# FPGA_RAM.net
KiCad netlist of a schematic drawn in Altium Designer
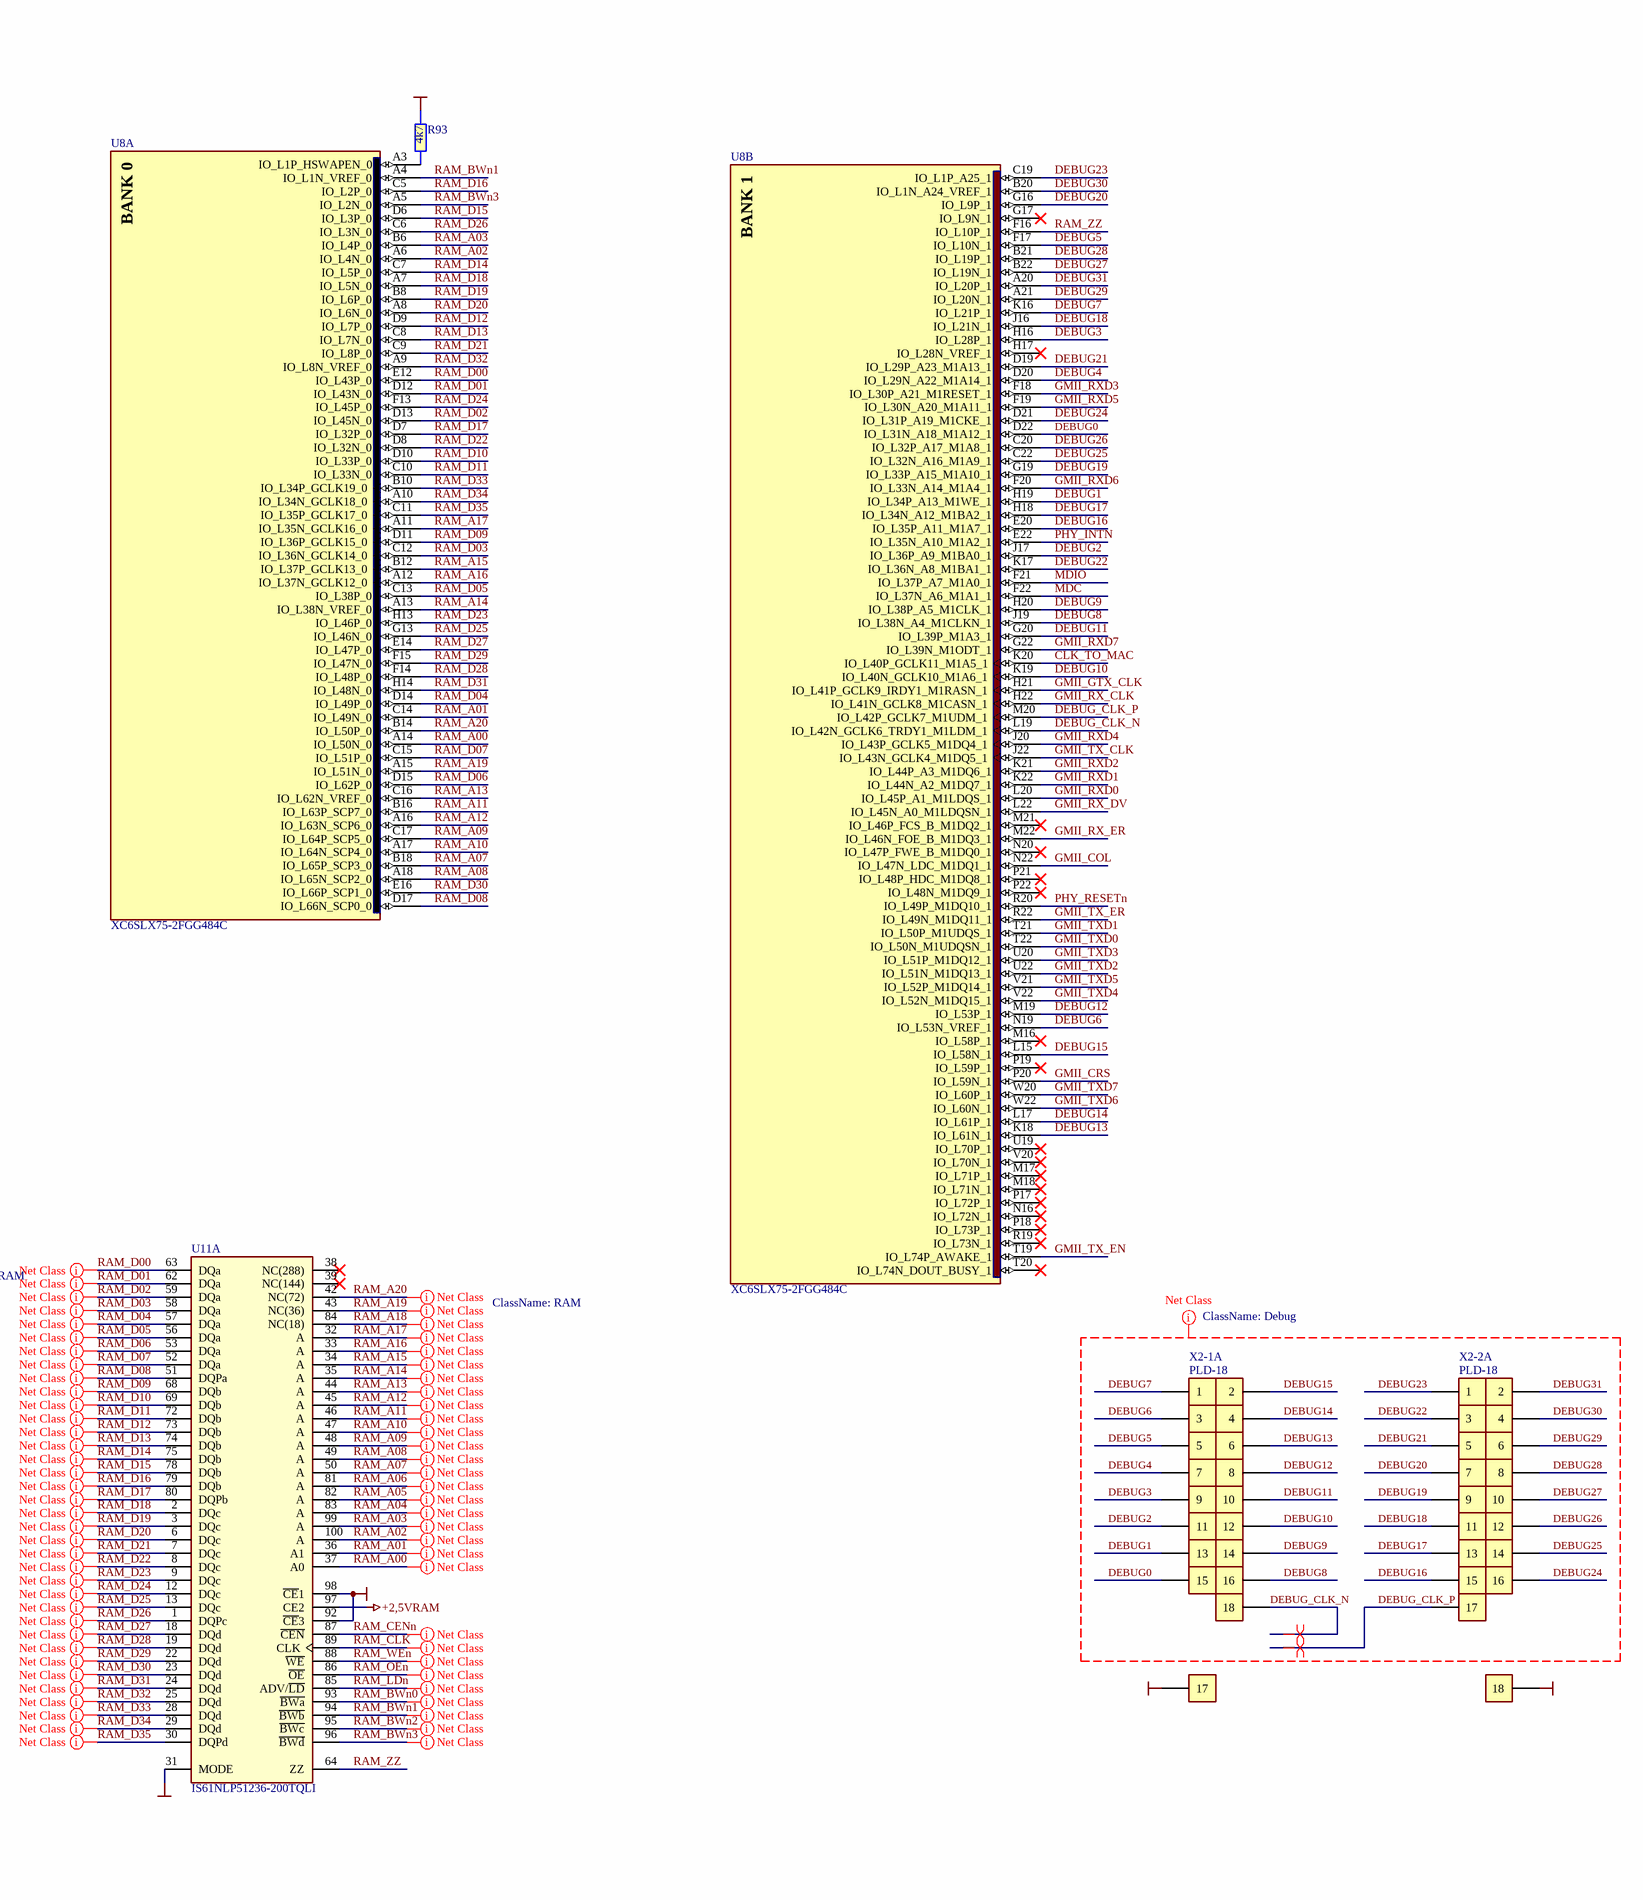
[diagram p0: FPGA_RAM.SchDoc, left]
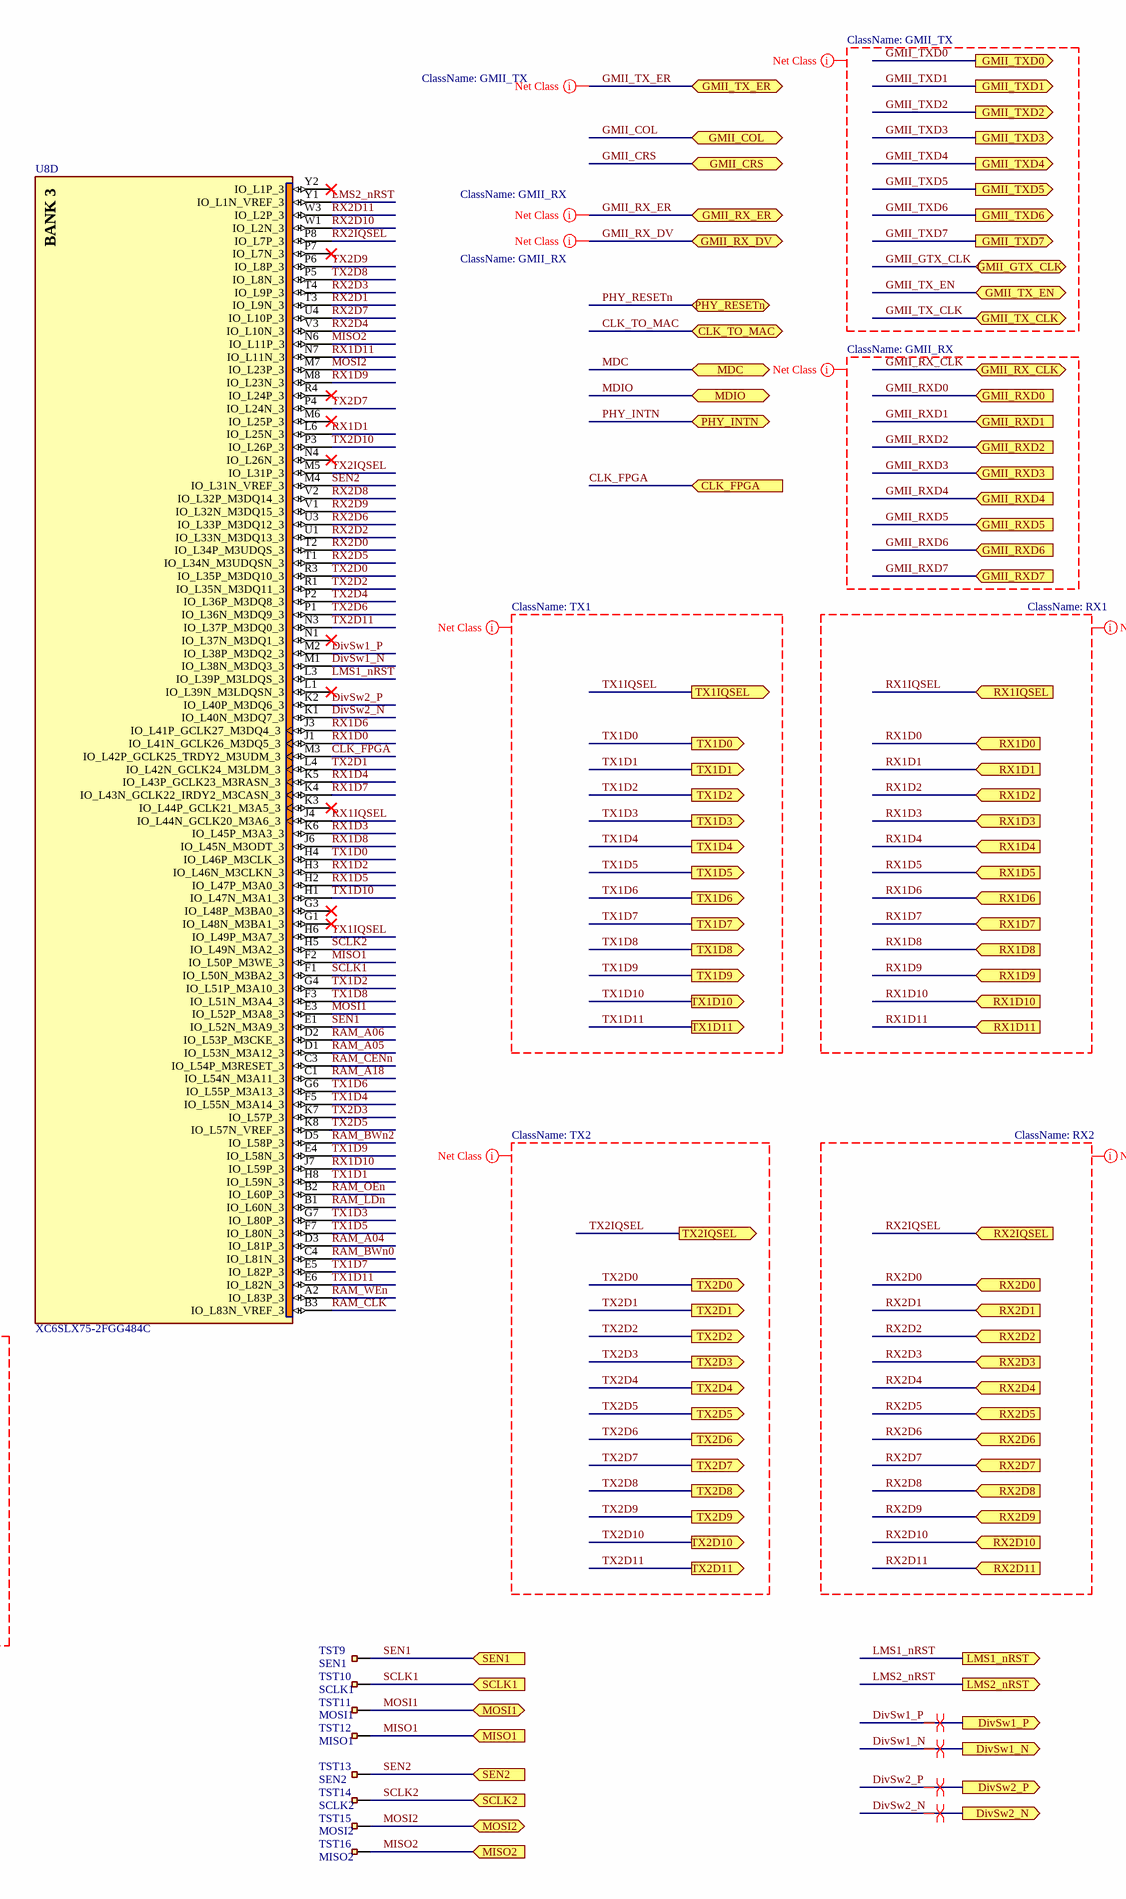
[diagram p1: FPGA_RAM.SchDoc, right]

(export (version "E")
  (design (tool "Eeschema 10.0.6"))
  (components
    (comp (ref "R93")
      (value "4k7")
      (footprint "R0603-PHILLIPS")
      (description "Резистор")
      (fields (field (name "MANUFACTURER") "YAGEO") (field (name "TOLERANCE") "5%"))
      (libsource (lib "altium-import") (part "root_2_R0603_"))
    )
    (comp (ref "TST9")
      (value "SEN1")
      (footprint "kp40x40")
      (description "Контактна  площадка")
      (fields (field (name "MANUFACTURER") "Конструктив"))
      (libsource (lib "Connectors") (part "KP"))
    )
    (comp (ref "TST10")
      (value "SCLK1")
      (footprint "kp40x40")
      (description "Контактна  площадка")
      (fields (field (name "MANUFACTURER") "Конструктив"))
      (libsource (lib "Connectors") (part "KP"))
    )
    (comp (ref "TST11")
      (value "MOSI1")
      (footprint "kp40x40")
      (description "Контактна  площадка")
      (fields (field (name "MANUFACTURER") "Конструктив"))
      (libsource (lib "Connectors") (part "KP"))
    )
    (comp (ref "TST12")
      (value "MISO1")
      (footprint "kp40x40")
      (description "Контактна  площадка")
      (fields (field (name "MANUFACTURER") "Конструктив"))
      (libsource (lib "Connectors") (part "KP"))
    )
    (comp (ref "TST13")
      (value "SEN2")
      (footprint "kp40x40")
      (description "Контактна  площадка")
      (fields (field (name "MANUFACTURER") "Конструктив"))
      (libsource (lib "Connectors") (part "KP"))
    )
    (comp (ref "TST14")
      (value "SCLK2")
      (footprint "kp40x40")
      (description "Контактна  площадка")
      (fields (field (name "MANUFACTURER") "Конструктив"))
      (libsource (lib "Connectors") (part "KP"))
    )
    (comp (ref "TST15")
      (value "MOSI2")
      (footprint "kp40x40")
      (description "Контактна  площадка")
      (fields (field (name "MANUFACTURER") "Конструктив"))
      (libsource (lib "Connectors") (part "KP"))
    )
    (comp (ref "TST16")
      (value "MISO2")
      (footprint "kp40x40")
      (description "Контактна  площадка")
      (fields (field (name "MANUFACTURER") "Конструктив"))
      (libsource (lib "Connectors") (part "KP"))
    )
    (comp (ref "U8")
      (value "XC6SLX75-2FGG484C")
      (footprint "FBGA484")
      (fields (field (name "MANUFACTURER") "Xilinx"))
      (libsource (lib "MicroCircuitsM-Z") (part "XC6SLX75-2FGG484C"))
    )
    (comp (ref "U11")
      (value "IS61NLP51236-200TQLI")
      (footprint "QFP-10020X14/0.65]")
      (description "Микросхема")
      (fields (field (name "MANUFACTURER") "ISSI"))
      (libsource (lib "MicroCircuits0-L") (part "CY7C1354C-166AXI"))
    )
    (comp (ref "X2-1")
      (value "PLD-18")
      (footprint "PLD-18")
      (description "Разъем")
      (fields (field (name "MANUFACTURER") "BM"))
      (libsource (lib "") (part "PLD-18_1"))
    )
    (comp (ref "X2-2")
      (value "PLD-18")
      (footprint "PLD-18")
      (description "Разъем")
      (fields (field (name "MANUFACTURER") "BM"))
      (libsource (lib "") (part "PLD-18_1"))
    )
  )
  (nets
    (net (code "1") (name "+2,5VRAM") (class "Default")
      (node (ref "U11") (pin "97") (pinfunction "CE2_97") (pintype "passive"))
    )
    (net (code "2") (name "/CLK_FPGA") (class "Default")
      (node (ref "U8") (pin "M3") (pinfunction "IO_L42P_GCLK25_TRDY2_M3UDM_3_M3") (pintype "bidirectional"))
    )
    (net (code "3") (name "/CLK_TO_MAC") (class "Default")
      (node (ref "U8") (pin "K20") (pinfunction "IO_L40P_GCLK11_M1A5_1_K20") (pintype "bidirectional"))
    )
    (net (code "4") (name "/DEBUG0") (class "Default")
      (node (ref "U8") (pin "D22") (pinfunction "IO_L31N_A18_M1A12_1_D22") (pintype "bidirectional"))
      (node (ref "X2-1") (pin "15") (pinfunction "15_15") (pintype "passive"))
    )
    (net (code "5") (name "/DEBUG1") (class "Default")
      (node (ref "U8") (pin "H19") (pinfunction "IO_L34P_A13_M1WE_1_H19") (pintype "bidirectional"))
      (node (ref "X2-1") (pin "13") (pinfunction "13_13") (pintype "passive"))
    )
    (net (code "6") (name "/DEBUG2") (class "Default")
      (node (ref "U8") (pin "J17") (pinfunction "IO_L36P_A9_M1BA0_1_J17") (pintype "bidirectional"))
      (node (ref "X2-1") (pin "11") (pinfunction "11_11") (pintype "passive"))
    )
    (net (code "7") (name "/DEBUG3") (class "Default")
      (node (ref "U8") (pin "H16") (pinfunction "IO_L28P_1_H16") (pintype "bidirectional"))
      (node (ref "X2-1") (pin "9") (pinfunction "9_9") (pintype "passive"))
    )
    (net (code "8") (name "/DEBUG4") (class "Default")
      (node (ref "U8") (pin "D20") (pinfunction "IO_L29N_A22_M1A14_1_D20") (pintype "bidirectional"))
      (node (ref "X2-1") (pin "7") (pinfunction "7_7") (pintype "passive"))
    )
    (net (code "9") (name "/DEBUG5") (class "Default")
      (node (ref "U8") (pin "F17") (pinfunction "IO_L10N_1_F17") (pintype "bidirectional"))
      (node (ref "X2-1") (pin "5") (pinfunction "5_5") (pintype "passive"))
    )
    (net (code "10") (name "/DEBUG6") (class "Default")
      (node (ref "U8") (pin "N19") (pinfunction "IO_L53N_VREF_1_N19") (pintype "bidirectional"))
      (node (ref "X2-1") (pin "3") (pinfunction "3_3") (pintype "passive"))
    )
    (net (code "11") (name "/DEBUG7") (class "Default")
      (node (ref "U8") (pin "K16") (pinfunction "IO_L21P_1_K16") (pintype "bidirectional"))
      (node (ref "X2-1") (pin "1") (pinfunction "1_1") (pintype "passive"))
    )
    (net (code "12") (name "/DEBUG8") (class "Default")
      (node (ref "U8") (pin "J19") (pinfunction "IO_L38N_A4_M1CLKN_1_J19") (pintype "bidirectional"))
      (node (ref "X2-1") (pin "16") (pinfunction "16_16") (pintype "passive"))
    )
    (net (code "13") (name "/DEBUG9") (class "Default")
      (node (ref "U8") (pin "H20") (pinfunction "IO_L38P_A5_M1CLK_1_H20") (pintype "bidirectional"))
      (node (ref "X2-1") (pin "14") (pinfunction "14_14") (pintype "passive"))
    )
    (net (code "14") (name "/DEBUG10") (class "Default")
      (node (ref "U8") (pin "K19") (pinfunction "IO_L40N_GCLK10_M1A6_1_K19") (pintype "bidirectional"))
      (node (ref "X2-1") (pin "12") (pinfunction "12_12") (pintype "passive"))
    )
    (net (code "15") (name "/DEBUG11") (class "Default")
      (node (ref "U8") (pin "G20") (pinfunction "IO_L39P_M1A3_1_G20") (pintype "bidirectional"))
      (node (ref "X2-1") (pin "10") (pinfunction "10_10") (pintype "passive"))
    )
    (net (code "16") (name "/DEBUG12") (class "Default")
      (node (ref "U8") (pin "M19") (pinfunction "IO_L53P_1_M19") (pintype "bidirectional"))
      (node (ref "X2-1") (pin "8") (pinfunction "8_8") (pintype "passive"))
    )
    (net (code "17") (name "/DEBUG13") (class "Default")
      (node (ref "U8") (pin "K18") (pinfunction "IO_L61N_1_K18") (pintype "bidirectional"))
      (node (ref "X2-1") (pin "6") (pinfunction "6_6") (pintype "passive"))
    )
    (net (code "18") (name "/DEBUG14") (class "Default")
      (node (ref "U8") (pin "L17") (pinfunction "IO_L61P_1_L17") (pintype "bidirectional"))
      (node (ref "X2-1") (pin "4") (pinfunction "4_4") (pintype "passive"))
    )
    (net (code "19") (name "/DEBUG15") (class "Default")
      (node (ref "U8") (pin "L15") (pinfunction "IO_L58N_1_L15") (pintype "bidirectional"))
      (node (ref "X2-1") (pin "2") (pinfunction "2_2") (pintype "passive"))
    )
    (net (code "20") (name "/DEBUG16") (class "Default")
      (node (ref "U8") (pin "E20") (pinfunction "IO_L35P_A11_M1A7_1_E20") (pintype "bidirectional"))
      (node (ref "X2-2") (pin "15") (pinfunction "15_15") (pintype "passive"))
    )
    (net (code "21") (name "/DEBUG17") (class "Default")
      (node (ref "U8") (pin "H18") (pinfunction "IO_L34N_A12_M1BA2_1_H18") (pintype "bidirectional"))
      (node (ref "X2-2") (pin "13") (pinfunction "13_13") (pintype "passive"))
    )
    (net (code "22") (name "/DEBUG18") (class "Default")
      (node (ref "U8") (pin "J16") (pinfunction "IO_L21N_1_J16") (pintype "bidirectional"))
      (node (ref "X2-2") (pin "11") (pinfunction "11_11") (pintype "passive"))
    )
    (net (code "23") (name "/DEBUG19") (class "Default")
      (node (ref "U8") (pin "G19") (pinfunction "IO_L33P_A15_M1A10_1_G19") (pintype "bidirectional"))
      (node (ref "X2-2") (pin "9") (pinfunction "9_9") (pintype "passive"))
    )
    (net (code "24") (name "/DEBUG20") (class "Default")
      (node (ref "U8") (pin "G16") (pinfunction "IO_L9P_1_G16") (pintype "bidirectional"))
      (node (ref "X2-2") (pin "7") (pinfunction "7_7") (pintype "passive"))
    )
    (net (code "25") (name "/DEBUG21") (class "Default")
      (node (ref "U8") (pin "D19") (pinfunction "IO_L29P_A23_M1A13_1_D19") (pintype "bidirectional"))
      (node (ref "X2-2") (pin "5") (pinfunction "5_5") (pintype "passive"))
    )
    (net (code "26") (name "/DEBUG22") (class "Default")
      (node (ref "U8") (pin "K17") (pinfunction "IO_L36N_A8_M1BA1_1_K17") (pintype "bidirectional"))
      (node (ref "X2-2") (pin "3") (pinfunction "3_3") (pintype "passive"))
    )
    (net (code "27") (name "/DEBUG23") (class "Default")
      (node (ref "U8") (pin "C19") (pinfunction "IO_L1P_A25_1_C19") (pintype "bidirectional"))
      (node (ref "X2-2") (pin "1") (pinfunction "1_1") (pintype "passive"))
    )
    (net (code "28") (name "/DEBUG24") (class "Default")
      (node (ref "U8") (pin "D21") (pinfunction "IO_L31P_A19_M1CKE_1_D21") (pintype "bidirectional"))
      (node (ref "X2-2") (pin "16") (pinfunction "16_16") (pintype "passive"))
    )
    (net (code "29") (name "/DEBUG25") (class "Default")
      (node (ref "U8") (pin "C22") (pinfunction "IO_L32N_A16_M1A9_1_C22") (pintype "bidirectional"))
      (node (ref "X2-2") (pin "14") (pinfunction "14_14") (pintype "passive"))
    )
    (net (code "30") (name "/DEBUG26") (class "Default")
      (node (ref "U8") (pin "C20") (pinfunction "IO_L32P_A17_M1A8_1_C20") (pintype "bidirectional"))
      (node (ref "X2-2") (pin "12") (pinfunction "12_12") (pintype "passive"))
    )
    (net (code "31") (name "/DEBUG27") (class "Default")
      (node (ref "U8") (pin "B22") (pinfunction "IO_L19N_1_B22") (pintype "bidirectional"))
      (node (ref "X2-2") (pin "10") (pinfunction "10_10") (pintype "passive"))
    )
    (net (code "32") (name "/DEBUG28") (class "Default")
      (node (ref "U8") (pin "B21") (pinfunction "IO_L19P_1_B21") (pintype "bidirectional"))
      (node (ref "X2-2") (pin "8") (pinfunction "8_8") (pintype "passive"))
    )
    (net (code "33") (name "/DEBUG29") (class "Default")
      (node (ref "U8") (pin "A21") (pinfunction "IO_L20N_1_A21") (pintype "bidirectional"))
      (node (ref "X2-2") (pin "6") (pinfunction "6_6") (pintype "passive"))
    )
    (net (code "34") (name "/DEBUG30") (class "Default")
      (node (ref "U8") (pin "B20") (pinfunction "IO_L1N_A24_VREF_1_B20") (pintype "bidirectional"))
      (node (ref "X2-2") (pin "4") (pinfunction "4_4") (pintype "passive"))
    )
    (net (code "35") (name "/DEBUG31") (class "Default")
      (node (ref "U8") (pin "A20") (pinfunction "IO_L20P_1_A20") (pintype "bidirectional"))
      (node (ref "X2-2") (pin "2") (pinfunction "2_2") (pintype "passive"))
    )
    (net (code "36") (name "/DEBUG_CLK_N") (class "Default")
      (node (ref "U8") (pin "L19") (pinfunction "IO_L42N_GCLK6_TRDY1_M1LDM_1_L19") (pintype "bidirectional"))
      (node (ref "X2-1") (pin "18") (pinfunction "18_18") (pintype "passive"))
    )
    (net (code "37") (name "/DEBUG_CLK_P") (class "Default")
      (node (ref "U8") (pin "M20") (pinfunction "IO_L42P_GCLK7_M1UDM_1_M20") (pintype "bidirectional"))
      (node (ref "X2-2") (pin "17") (pinfunction "17_17") (pintype "passive"))
    )
    (net (code "38") (name "/DivSw1_N") (class "Default")
      (node (ref "U8") (pin "M1") (pinfunction "IO_L38N_M3DQ3_3_M1") (pintype "bidirectional"))
    )
    (net (code "39") (name "/DivSw1_P") (class "Default")
      (node (ref "U8") (pin "M2") (pinfunction "IO_L38P_M3DQ2_3_M2") (pintype "bidirectional"))
    )
    (net (code "40") (name "/DivSw2_N") (class "Default")
      (node (ref "U8") (pin "K1") (pinfunction "IO_L40N_M3DQ7_3_K1") (pintype "bidirectional"))
    )
    (net (code "41") (name "/DivSw2_P") (class "Default")
      (node (ref "U8") (pin "K2") (pinfunction "IO_L40P_M3DQ6_3_K2") (pintype "bidirectional"))
    )
    (net (code "42") (name "/GMII_COL") (class "Default")
      (node (ref "U8") (pin "N22") (pinfunction "IO_L47N_LDC_M1DQ1_1_N22") (pintype "bidirectional"))
    )
    (net (code "43") (name "/GMII_CRS") (class "Default")
      (node (ref "U8") (pin "P20") (pinfunction "IO_L59N_1_P20") (pintype "bidirectional"))
    )
    (net (code "44") (name "/GMII_GTX_CLK") (class "Default")
      (node (ref "U8") (pin "H21") (pinfunction "IO_L41P_GCLK9_IRDY1_M1RASN_1_H21") (pintype "bidirectional"))
    )
    (net (code "45") (name "/GMII_RXD0") (class "Default")
      (node (ref "U8") (pin "L20") (pinfunction "IO_L45P_A1_M1LDQS_1_L20") (pintype "bidirectional"))
    )
    (net (code "46") (name "/GMII_RXD1") (class "Default")
      (node (ref "U8") (pin "K22") (pinfunction "IO_L44N_A2_M1DQ7_1_K22") (pintype "bidirectional"))
    )
    (net (code "47") (name "/GMII_RXD2") (class "Default")
      (node (ref "U8") (pin "K21") (pinfunction "IO_L44P_A3_M1DQ6_1_K21") (pintype "bidirectional"))
    )
    (net (code "48") (name "/GMII_RXD3") (class "Default")
      (node (ref "U8") (pin "F18") (pinfunction "IO_L30P_A21_M1RESET_1_F18") (pintype "bidirectional"))
    )
    (net (code "49") (name "/GMII_RXD4") (class "Default")
      (node (ref "U8") (pin "J20") (pinfunction "IO_L43P_GCLK5_M1DQ4_1_J20") (pintype "bidirectional"))
    )
    (net (code "50") (name "/GMII_RXD5") (class "Default")
      (node (ref "U8") (pin "F19") (pinfunction "IO_L30N_A20_M1A11_1_F19") (pintype "bidirectional"))
    )
    (net (code "51") (name "/GMII_RXD6") (class "Default")
      (node (ref "U8") (pin "F20") (pinfunction "IO_L33N_A14_M1A4_1_F20") (pintype "bidirectional"))
    )
    (net (code "52") (name "/GMII_RXD7") (class "Default")
      (node (ref "U8") (pin "G22") (pinfunction "IO_L39N_M1ODT_1_G22") (pintype "bidirectional"))
    )
    (net (code "53") (name "/GMII_RX_CLK") (class "Default")
      (node (ref "U8") (pin "H22") (pinfunction "IO_L41N_GCLK8_M1CASN_1_H22") (pintype "bidirectional"))
    )
    (net (code "54") (name "/GMII_RX_DV") (class "Default")
      (node (ref "U8") (pin "L22") (pinfunction "IO_L45N_A0_M1LDQSN_1_L22") (pintype "bidirectional"))
    )
    (net (code "55") (name "/GMII_RX_ER") (class "Default")
      (node (ref "U8") (pin "M22") (pinfunction "IO_L46N_FOE_B_M1DQ3_1_M22") (pintype "bidirectional"))
    )
    (net (code "56") (name "/GMII_TXD0") (class "Default")
      (node (ref "U8") (pin "T22") (pinfunction "IO_L50N_M1UDQSN_1_T22") (pintype "bidirectional"))
    )
    (net (code "57") (name "/GMII_TXD1") (class "Default")
      (node (ref "U8") (pin "T21") (pinfunction "IO_L50P_M1UDQS_1_T21") (pintype "bidirectional"))
    )
    (net (code "58") (name "/GMII_TXD2") (class "Default")
      (node (ref "U8") (pin "U22") (pinfunction "IO_L51N_M1DQ13_1_U22") (pintype "bidirectional"))
    )
    (net (code "59") (name "/GMII_TXD3") (class "Default")
      (node (ref "U8") (pin "U20") (pinfunction "IO_L51P_M1DQ12_1_U20") (pintype "bidirectional"))
    )
    (net (code "60") (name "/GMII_TXD4") (class "Default")
      (node (ref "U8") (pin "V22") (pinfunction "IO_L52N_M1DQ15_1_V22") (pintype "bidirectional"))
    )
    (net (code "61") (name "/GMII_TXD5") (class "Default")
      (node (ref "U8") (pin "V21") (pinfunction "IO_L52P_M1DQ14_1_V21") (pintype "bidirectional"))
    )
    (net (code "62") (name "/GMII_TXD6") (class "Default")
      (node (ref "U8") (pin "W22") (pinfunction "IO_L60N_1_W22") (pintype "bidirectional"))
    )
    (net (code "63") (name "/GMII_TXD7") (class "Default")
      (node (ref "U8") (pin "W20") (pinfunction "IO_L60P_1_W20") (pintype "bidirectional"))
    )
    (net (code "64") (name "/GMII_TX_CLK") (class "Default")
      (node (ref "U8") (pin "J22") (pinfunction "IO_L43N_GCLK4_M1DQ5_1_J22") (pintype "bidirectional"))
    )
    (net (code "65") (name "/GMII_TX_EN") (class "Default")
      (node (ref "U8") (pin "T19") (pinfunction "IO_L74P_AWAKE_1_T19") (pintype "bidirectional"))
    )
    (net (code "66") (name "/GMII_TX_ER") (class "Default")
      (node (ref "U8") (pin "R22") (pinfunction "IO_L49N_M1DQ11_1_R22") (pintype "bidirectional"))
    )
    (net (code "67") (name "/LMS1_nRST") (class "Default")
      (node (ref "U8") (pin "L3") (pinfunction "IO_L39P_M3LDQS_3_L3") (pintype "bidirectional"))
    )
    (net (code "68") (name "/LMS2_nRST") (class "Default")
      (node (ref "U8") (pin "Y1") (pinfunction "IO_L1N_VREF_3_Y1") (pintype "bidirectional"))
    )
    (net (code "69") (name "/MDC") (class "Default")
      (node (ref "U8") (pin "F22") (pinfunction "IO_L37N_A6_M1A1_1_F22") (pintype "bidirectional"))
    )
    (net (code "70") (name "/MDIO") (class "Default")
      (node (ref "U8") (pin "F21") (pinfunction "IO_L37P_A7_M1A0_1_F21") (pintype "bidirectional"))
    )
    (net (code "71") (name "/MISO1") (class "Default")
      (node (ref "TST12") (pin "1") (pinfunction "1_1") (pintype "passive"))
      (node (ref "U8") (pin "F2") (pinfunction "IO_L50P_M3WE_3_F2") (pintype "bidirectional"))
    )
    (net (code "72") (name "/MISO2") (class "Default")
      (node (ref "TST16") (pin "1") (pinfunction "1_1") (pintype "passive"))
      (node (ref "U8") (pin "N6") (pinfunction "IO_L11P_3_N6") (pintype "bidirectional"))
    )
    (net (code "73") (name "/MOSI1") (class "Default")
      (node (ref "TST11") (pin "1") (pinfunction "1_1") (pintype "passive"))
      (node (ref "U8") (pin "E3") (pinfunction "IO_L52P_M3A8_3_E3") (pintype "bidirectional"))
    )
    (net (code "74") (name "/MOSI2") (class "Default")
      (node (ref "TST15") (pin "1") (pinfunction "1_1") (pintype "passive"))
      (node (ref "U8") (pin "M7") (pinfunction "IO_L23P_3_M7") (pintype "bidirectional"))
    )
    (net (code "75") (name "/PHY_INTN") (class "Default")
      (node (ref "U8") (pin "E22") (pinfunction "IO_L35N_A10_M1A2_1_E22") (pintype "bidirectional"))
    )
    (net (code "76") (name "/PHY_RESETn") (class "Default")
      (node (ref "U8") (pin "R20") (pinfunction "IO_L49P_M1DQ10_1_R20") (pintype "bidirectional"))
    )
    (net (code "77") (name "/RAM_A00") (class "Default")
      (node (ref "U11") (pin "37") (pinfunction "A0_37") (pintype "passive"))
      (node (ref "U8") (pin "A14") (pinfunction "IO_L50N_0_A14") (pintype "bidirectional"))
    )
    (net (code "78") (name "/RAM_A01") (class "Default")
      (node (ref "U11") (pin "36") (pinfunction "A1_36") (pintype "passive"))
      (node (ref "U8") (pin "C14") (pinfunction "IO_L49N_0_C14") (pintype "bidirectional"))
    )
    (net (code "79") (name "/RAM_A02") (class "Default")
      (node (ref "U11") (pin "100") (pinfunction "A_100") (pintype "passive"))
      (node (ref "U8") (pin "A6") (pinfunction "IO_L4N_0_A6") (pintype "bidirectional"))
    )
    (net (code "80") (name "/RAM_A03") (class "Default")
      (node (ref "U11") (pin "99") (pinfunction "A_99") (pintype "passive"))
      (node (ref "U8") (pin "B6") (pinfunction "IO_L4P_0_B6") (pintype "bidirectional"))
    )
    (net (code "81") (name "/RAM_A04") (class "Default")
      (node (ref "U11") (pin "83") (pinfunction "A_83") (pintype "passive"))
      (node (ref "U8") (pin "D3") (pinfunction "IO_L81P_3_D3") (pintype "bidirectional"))
    )
    (net (code "82") (name "/RAM_A05") (class "Default")
      (node (ref "U11") (pin "82") (pinfunction "A_82") (pintype "passive"))
      (node (ref "U8") (pin "D1") (pinfunction "IO_L53N_M3A12_3_D1") (pintype "bidirectional"))
    )
    (net (code "83") (name "/RAM_A06") (class "Default")
      (node (ref "U11") (pin "81") (pinfunction "A_81") (pintype "passive"))
      (node (ref "U8") (pin "D2") (pinfunction "IO_L53P_M3CKE_3_D2") (pintype "bidirectional"))
    )
    (net (code "84") (name "/RAM_A07") (class "Default")
      (node (ref "U11") (pin "50") (pinfunction "A_50") (pintype "passive"))
      (node (ref "U8") (pin "B18") (pinfunction "IO_L65P_SCP3_0_B18") (pintype "bidirectional"))
    )
    (net (code "85") (name "/RAM_A08") (class "Default")
      (node (ref "U11") (pin "49") (pinfunction "A_49") (pintype "passive"))
      (node (ref "U8") (pin "A18") (pinfunction "IO_L65N_SCP2_0_A18") (pintype "bidirectional"))
    )
    (net (code "86") (name "/RAM_A09") (class "Default")
      (node (ref "U11") (pin "48") (pinfunction "A_48") (pintype "passive"))
      (node (ref "U8") (pin "C17") (pinfunction "IO_L64P_SCP5_0_C17") (pintype "bidirectional"))
    )
    (net (code "87") (name "/RAM_A10") (class "Default")
      (node (ref "U11") (pin "47") (pinfunction "A_47") (pintype "passive"))
      (node (ref "U8") (pin "A17") (pinfunction "IO_L64N_SCP4_0_A17") (pintype "bidirectional"))
    )
    (net (code "88") (name "/RAM_A11") (class "Default")
      (node (ref "U11") (pin "46") (pinfunction "A_46") (pintype "passive"))
      (node (ref "U8") (pin "B16") (pinfunction "IO_L63P_SCP7_0_B16") (pintype "bidirectional"))
    )
    (net (code "89") (name "/RAM_A12") (class "Default")
      (node (ref "U11") (pin "45") (pinfunction "A_45") (pintype "passive"))
      (node (ref "U8") (pin "A16") (pinfunction "IO_L63N_SCP6_0_A16") (pintype "bidirectional"))
    )
    (net (code "90") (name "/RAM_A13") (class "Default")
      (node (ref "U11") (pin "44") (pinfunction "A_44") (pintype "passive"))
      (node (ref "U8") (pin "C16") (pinfunction "IO_L62N_VREF_0_C16") (pintype "bidirectional"))
    )
    (net (code "91") (name "/RAM_A14") (class "Default")
      (node (ref "U11") (pin "35") (pinfunction "A_35") (pintype "passive"))
      (node (ref "U8") (pin "A13") (pinfunction "IO_L38N_VREF_0_A13") (pintype "bidirectional"))
    )
    (net (code "92") (name "/RAM_A15") (class "Default")
      (node (ref "U11") (pin "34") (pinfunction "A_34") (pintype "passive"))
      (node (ref "U8") (pin "B12") (pinfunction "IO_L37P_GCLK13_0_B12") (pintype "bidirectional"))
    )
    (net (code "93") (name "/RAM_A16") (class "Default")
      (node (ref "U11") (pin "33") (pinfunction "A_33") (pintype "passive"))
      (node (ref "U8") (pin "A12") (pinfunction "IO_L37N_GCLK12_0_A12") (pintype "bidirectional"))
    )
    (net (code "94") (name "/RAM_A17") (class "Default")
      (node (ref "U11") (pin "32") (pinfunction "A_32") (pintype "passive"))
      (node (ref "U8") (pin "A11") (pinfunction "IO_L35N_GCLK16_0_A11") (pintype "bidirectional"))
    )
    (net (code "95") (name "/RAM_A18") (class "Default")
      (node (ref "U11") (pin "84") (pinfunction "NC(18)_84") (pintype "passive"))
      (node (ref "U8") (pin "C1") (pinfunction "IO_L54N_M3A11_3_C1") (pintype "bidirectional"))
    )
    (net (code "96") (name "/RAM_A19") (class "Default")
      (node (ref "U11") (pin "43") (pinfunction "NC(36)_43") (pintype "passive"))
      (node (ref "U8") (pin "A15") (pinfunction "IO_L51N_0_A15") (pintype "bidirectional"))
    )
    (net (code "97") (name "/RAM_A20") (class "Default")
      (node (ref "U11") (pin "42") (pinfunction "NC(72)_42") (pintype "passive"))
      (node (ref "U8") (pin "B14") (pinfunction "IO_L50P_0_B14") (pintype "bidirectional"))
    )
    (net (code "98") (name "/RAM_BWn0") (class "Default")
      (node (ref "U11") (pin "93") (pinfunction "~{BWa}_93") (pintype "passive"))
      (node (ref "U8") (pin "C4") (pinfunction "IO_L81N_3_C4") (pintype "bidirectional"))
    )
    (net (code "99") (name "/RAM_BWn1") (class "Default")
      (node (ref "U11") (pin "94") (pinfunction "~{BWb}_94") (pintype "passive"))
      (node (ref "U8") (pin "A4") (pinfunction "IO_L1N_VREF_0_A4") (pintype "bidirectional"))
    )
    (net (code "100") (name "/RAM_BWn2") (class "Default")
      (node (ref "U11") (pin "95") (pinfunction "~{BWc}_95") (pintype "passive"))
      (node (ref "U8") (pin "D5") (pinfunction "IO_L58P_3_D5") (pintype "bidirectional"))
    )
    (net (code "101") (name "/RAM_BWn3") (class "Default")
      (node (ref "U11") (pin "96") (pinfunction "~{BWd}_96") (pintype "passive"))
      (node (ref "U8") (pin "A5") (pinfunction "IO_L2N_0_A5") (pintype "bidirectional"))
    )
    (net (code "102") (name "/RAM_CENn") (class "Default")
      (node (ref "U11") (pin "87") (pinfunction "~{CEN}_87") (pintype "passive"))
      (node (ref "U8") (pin "C3") (pinfunction "IO_L54P_M3RESET_3_C3") (pintype "bidirectional"))
    )
    (net (code "103") (name "/RAM_CLK") (class "Default")
      (node (ref "U11") (pin "89") (pinfunction "CLK_89") (pintype "passive"))
      (node (ref "U8") (pin "B3") (pinfunction "IO_L83N_VREF_3_B3") (pintype "bidirectional"))
    )
    (net (code "104") (name "/RAM_D00") (class "Default")
      (node (ref "U11") (pin "63") (pinfunction "DQa_63") (pintype "passive"))
      (node (ref "U8") (pin "E12") (pinfunction "IO_L43P_0_E12") (pintype "bidirectional"))
    )
    (net (code "105") (name "/RAM_D01") (class "Default")
      (node (ref "U11") (pin "62") (pinfunction "DQa_62") (pintype "passive"))
      (node (ref "U8") (pin "D12") (pinfunction "IO_L43N_0_D12") (pintype "bidirectional"))
    )
    (net (code "106") (name "/RAM_D02") (class "Default")
      (node (ref "U11") (pin "59") (pinfunction "DQa_59") (pintype "passive"))
      (node (ref "U8") (pin "D13") (pinfunction "IO_L45N_0_D13") (pintype "bidirectional"))
    )
    (net (code "107") (name "/RAM_D03") (class "Default")
      (node (ref "U11") (pin "58") (pinfunction "DQa_58") (pintype "passive"))
      (node (ref "U8") (pin "C12") (pinfunction "IO_L36N_GCLK14_0_C12") (pintype "bidirectional"))
    )
    (net (code "108") (name "/RAM_D04") (class "Default")
      (node (ref "U11") (pin "57") (pinfunction "DQa_57") (pintype "passive"))
      (node (ref "U8") (pin "D14") (pinfunction "IO_L49P_0_D14") (pintype "bidirectional"))
    )
    (net (code "109") (name "/RAM_D05") (class "Default")
      (node (ref "U11") (pin "56") (pinfunction "DQa_56") (pintype "passive"))
      (node (ref "U8") (pin "C13") (pinfunction "IO_L38P_0_C13") (pintype "bidirectional"))
    )
    (net (code "110") (name "/RAM_D06") (class "Default")
      (node (ref "U11") (pin "53") (pinfunction "DQa_53") (pintype "passive"))
      (node (ref "U8") (pin "D15") (pinfunction "IO_L62P_0_D15") (pintype "bidirectional"))
    )
    (net (code "111") (name "/RAM_D07") (class "Default")
      (node (ref "U11") (pin "52") (pinfunction "DQa_52") (pintype "passive"))
      (node (ref "U8") (pin "C15") (pinfunction "IO_L51P_0_C15") (pintype "bidirectional"))
    )
    (net (code "112") (name "/RAM_D08") (class "Default")
      (node (ref "U11") (pin "51") (pinfunction "DQPa_51") (pintype "passive"))
      (node (ref "U8") (pin "D17") (pinfunction "IO_L66N_SCP0_0_D17") (pintype "bidirectional"))
    )
    (net (code "113") (name "/RAM_D09") (class "Default")
      (node (ref "U11") (pin "68") (pinfunction "DQb_68") (pintype "passive"))
      (node (ref "U8") (pin "D11") (pinfunction "IO_L36P_GCLK15_0_D11") (pintype "bidirectional"))
    )
    (net (code "114") (name "/RAM_D10") (class "Default")
      (node (ref "U11") (pin "69") (pinfunction "DQb_69") (pintype "passive"))
      (node (ref "U8") (pin "D10") (pinfunction "IO_L33P_0_D10") (pintype "bidirectional"))
    )
    (net (code "115") (name "/RAM_D11") (class "Default")
      (node (ref "U11") (pin "72") (pinfunction "DQb_72") (pintype "passive"))
      (node (ref "U8") (pin "C10") (pinfunction "IO_L33N_0_C10") (pintype "bidirectional"))
    )
    (net (code "116") (name "/RAM_D12") (class "Default")
      (node (ref "U11") (pin "73") (pinfunction "DQb_73") (pintype "passive"))
      (node (ref "U8") (pin "D9") (pinfunction "IO_L7P_0_D9") (pintype "bidirectional"))
    )
    (net (code "117") (name "/RAM_D13") (class "Default")
      (node (ref "U11") (pin "74") (pinfunction "DQb_74") (pintype "passive"))
      (node (ref "U8") (pin "C8") (pinfunction "IO_L7N_0_C8") (pintype "bidirectional"))
    )
    (net (code "118") (name "/RAM_D14") (class "Default")
      (node (ref "U11") (pin "75") (pinfunction "DQb_75") (pintype "passive"))
      (node (ref "U8") (pin "C7") (pinfunction "IO_L5P_0_C7") (pintype "bidirectional"))
    )
    (net (code "119") (name "/RAM_D15") (class "Default")
      (node (ref "U11") (pin "78") (pinfunction "DQb_78") (pintype "passive"))
      (node (ref "U8") (pin "D6") (pinfunction "IO_L3P_0_D6") (pintype "bidirectional"))
    )
    (net (code "120") (name "/RAM_D16") (class "Default")
      (node (ref "U11") (pin "79") (pinfunction "DQb_79") (pintype "passive"))
      (node (ref "U8") (pin "C5") (pinfunction "IO_L2P_0_C5") (pintype "bidirectional"))
    )
    (net (code "121") (name "/RAM_D17") (class "Default")
      (node (ref "U11") (pin "80") (pinfunction "DQPb_80") (pintype "passive"))
      (node (ref "U8") (pin "D7") (pinfunction "IO_L32P_0_D7") (pintype "bidirectional"))
    )
    (net (code "122") (name "/RAM_D18") (class "Default")
      (node (ref "U11") (pin "2") (pinfunction "DQc_2") (pintype "passive"))
      (node (ref "U8") (pin "A7") (pinfunction "IO_L5N_0_A7") (pintype "bidirectional"))
    )
    (net (code "123") (name "/RAM_D19") (class "Default")
      (node (ref "U11") (pin "3") (pinfunction "DQc_3") (pintype "passive"))
      (node (ref "U8") (pin "B8") (pinfunction "IO_L6P_0_B8") (pintype "bidirectional"))
    )
    (net (code "124") (name "/RAM_D20") (class "Default")
      (node (ref "U11") (pin "6") (pinfunction "DQc_6") (pintype "passive"))
      (node (ref "U8") (pin "A8") (pinfunction "IO_L6N_0_A8") (pintype "bidirectional"))
    )
    (net (code "125") (name "/RAM_D21") (class "Default")
      (node (ref "U11") (pin "7") (pinfunction "DQc_7") (pintype "passive"))
      (node (ref "U8") (pin "C9") (pinfunction "IO_L8P_0_C9") (pintype "bidirectional"))
    )
    (net (code "126") (name "/RAM_D22") (class "Default")
      (node (ref "U11") (pin "8") (pinfunction "DQc_8") (pintype "passive"))
      (node (ref "U8") (pin "D8") (pinfunction "IO_L32N_0_D8") (pintype "bidirectional"))
    )
    (net (code "127") (name "/RAM_D23") (class "Default")
      (node (ref "U11") (pin "9") (pinfunction "DQc_9") (pintype "passive"))
      (node (ref "U8") (pin "H13") (pinfunction "IO_L46P_0_H13") (pintype "bidirectional"))
    )
    (net (code "128") (name "/RAM_D24") (class "Default")
      (node (ref "U11") (pin "12") (pinfunction "DQc_12") (pintype "passive"))
      (node (ref "U8") (pin "F13") (pinfunction "IO_L45P_0_F13") (pintype "bidirectional"))
    )
    (net (code "129") (name "/RAM_D25") (class "Default")
      (node (ref "U11") (pin "13") (pinfunction "DQc_13") (pintype "passive"))
      (node (ref "U8") (pin "G13") (pinfunction "IO_L46N_0_G13") (pintype "bidirectional"))
    )
    (net (code "130") (name "/RAM_D26") (class "Default")
      (node (ref "U11") (pin "1") (pinfunction "DQPc_1") (pintype "passive"))
      (node (ref "U8") (pin "C6") (pinfunction "IO_L3N_0_C6") (pintype "bidirectional"))
    )
    (net (code "131") (name "/RAM_D27") (class "Default")
      (node (ref "U11") (pin "18") (pinfunction "DQd_18") (pintype "passive"))
      (node (ref "U8") (pin "E14") (pinfunction "IO_L47P_0_E14") (pintype "bidirectional"))
    )
    (net (code "132") (name "/RAM_D28") (class "Default")
      (node (ref "U11") (pin "19") (pinfunction "DQd_19") (pintype "passive"))
      (node (ref "U8") (pin "F14") (pinfunction "IO_L48P_0_F14") (pintype "bidirectional"))
    )
    (net (code "133") (name "/RAM_D29") (class "Default")
      (node (ref "U11") (pin "22") (pinfunction "DQd_22") (pintype "passive"))
      (node (ref "U8") (pin "F15") (pinfunction "IO_L47N_0_F15") (pintype "bidirectional"))
    )
    (net (code "134") (name "/RAM_D30") (class "Default")
      (node (ref "U11") (pin "23") (pinfunction "DQd_23") (pintype "passive"))
      (node (ref "U8") (pin "E16") (pinfunction "IO_L66P_SCP1_0_E16") (pintype "bidirectional"))
    )
    (net (code "135") (name "/RAM_D31") (class "Default")
      (node (ref "U11") (pin "24") (pinfunction "DQd_24") (pintype "passive"))
      (node (ref "U8") (pin "H14") (pinfunction "IO_L48N_0_H14") (pintype "bidirectional"))
    )
    (net (code "136") (name "/RAM_D32") (class "Default")
      (node (ref "U11") (pin "25") (pinfunction "DQd_25") (pintype "passive"))
      (node (ref "U8") (pin "A9") (pinfunction "IO_L8N_VREF_0_A9") (pintype "bidirectional"))
    )
    (net (code "137") (name "/RAM_D33") (class "Default")
      (node (ref "U11") (pin "28") (pinfunction "DQd_28") (pintype "passive"))
      (node (ref "U8") (pin "B10") (pinfunction "IO_L34P_GCLK19_0_B10") (pintype "bidirectional"))
    )
    (net (code "138") (name "/RAM_D34") (class "Default")
      (node (ref "U11") (pin "29") (pinfunction "DQd_29") (pintype "passive"))
      (node (ref "U8") (pin "A10") (pinfunction "IO_L34N_GCLK18_0_A10") (pintype "bidirectional"))
    )
    (net (code "139") (name "/RAM_D35") (class "Default")
      (node (ref "U11") (pin "30") (pinfunction "DQPd_30") (pintype "passive"))
      (node (ref "U8") (pin "C11") (pinfunction "IO_L35P_GCLK17_0_C11") (pintype "bidirectional"))
    )
    (net (code "140") (name "/RAM_LDn") (class "Default")
      (node (ref "U11") (pin "85") (pinfunction "ADV/~{LD}_85") (pintype "passive"))
      (node (ref "U8") (pin "B1") (pinfunction "IO_L60N_3_B1") (pintype "bidirectional"))
    )
    (net (code "141") (name "/RAM_OEn") (class "Default")
      (node (ref "U11") (pin "86") (pinfunction "~{OE}_86") (pintype "passive"))
      (node (ref "U8") (pin "B2") (pinfunction "IO_L60P_3_B2") (pintype "bidirectional"))
    )
    (net (code "142") (name "/RAM_WEn") (class "Default")
      (node (ref "U11") (pin "88") (pinfunction "~{WE}_88") (pintype "passive"))
      (node (ref "U8") (pin "A2") (pinfunction "IO_L83P_3_A2") (pintype "bidirectional"))
    )
    (net (code "143") (name "/RAM_ZZ") (class "Default")
      (node (ref "U11") (pin "64") (pinfunction "ZZ_64") (pintype "passive"))
      (node (ref "U8") (pin "F16") (pinfunction "IO_L10P_1_F16") (pintype "bidirectional"))
    )
    (net (code "144") (name "/RX1D0") (class "Default")
      (node (ref "U8") (pin "J1") (pinfunction "IO_L41N_GCLK26_M3DQ5_3_J1") (pintype "bidirectional"))
    )
    (net (code "145") (name "/RX1D1") (class "Default")
      (node (ref "U8") (pin "L6") (pinfunction "IO_L25N_3_L6") (pintype "bidirectional"))
    )
    (net (code "146") (name "/RX1D2") (class "Default")
      (node (ref "U8") (pin "H3") (pinfunction "IO_L46N_M3CLKN_3_H3") (pintype "bidirectional"))
    )
    (net (code "147") (name "/RX1D3") (class "Default")
      (node (ref "U8") (pin "K6") (pinfunction "IO_L45P_M3A3_3_K6") (pintype "bidirectional"))
    )
    (net (code "148") (name "/RX1D4") (class "Default")
      (node (ref "U8") (pin "K5") (pinfunction "IO_L43P_GCLK23_M3RASN_3_K5") (pintype "bidirectional"))
    )
    (net (code "149") (name "/RX1D5") (class "Default")
      (node (ref "U8") (pin "H2") (pinfunction "IO_L47P_M3A0_3_H2") (pintype "bidirectional"))
    )
    (net (code "150") (name "/RX1D6") (class "Default")
      (node (ref "U8") (pin "J3") (pinfunction "IO_L41P_GCLK27_M3DQ4_3_J3") (pintype "bidirectional"))
    )
    (net (code "151") (name "/RX1D7") (class "Default")
      (node (ref "U8") (pin "K4") (pinfunction "IO_L43N_GCLK22_IRDY2_M3CASN_3_K4") (pintype "bidirectional"))
    )
    (net (code "152") (name "/RX1D8") (class "Default")
      (node (ref "U8") (pin "J6") (pinfunction "IO_L45N_M3ODT_3_J6") (pintype "bidirectional"))
    )
    (net (code "153") (name "/RX1D9") (class "Default")
      (node (ref "U8") (pin "M8") (pinfunction "IO_L23N_3_M8") (pintype "bidirectional"))
    )
    (net (code "154") (name "/RX1D10") (class "Default")
      (node (ref "U8") (pin "J7") (pinfunction "IO_L59P_3_J7") (pintype "bidirectional"))
    )
    (net (code "155") (name "/RX1D11") (class "Default")
      (node (ref "U8") (pin "N7") (pinfunction "IO_L11N_3_N7") (pintype "bidirectional"))
    )
    (net (code "156") (name "/RX1IQSEL") (class "Default")
      (node (ref "U8") (pin "J4") (pinfunction "IO_L44N_GCLK20_M3A6_3_J4") (pintype "bidirectional"))
    )
    (net (code "157") (name "/RX2D0") (class "Default")
      (node (ref "U8") (pin "T2") (pinfunction "IO_L34P_M3UDQS_3_T2") (pintype "bidirectional"))
    )
    (net (code "158") (name "/RX2D1") (class "Default")
      (node (ref "U8") (pin "T3") (pinfunction "IO_L9N_3_T3") (pintype "bidirectional"))
    )
    (net (code "159") (name "/RX2D2") (class "Default")
      (node (ref "U8") (pin "U1") (pinfunction "IO_L33N_M3DQ13_3_U1") (pintype "bidirectional"))
    )
    (net (code "160") (name "/RX2D3") (class "Default")
      (node (ref "U8") (pin "T4") (pinfunction "IO_L9P_3_T4") (pintype "bidirectional"))
    )
    (net (code "161") (name "/RX2D4") (class "Default")
      (node (ref "U8") (pin "V3") (pinfunction "IO_L10N_3_V3") (pintype "bidirectional"))
    )
    (net (code "162") (name "/RX2D5") (class "Default")
      (node (ref "U8") (pin "T1") (pinfunction "IO_L34N_M3UDQSN_3_T1") (pintype "bidirectional"))
    )
    (net (code "163") (name "/RX2D6") (class "Default")
      (node (ref "U8") (pin "U3") (pinfunction "IO_L33P_M3DQ12_3_U3") (pintype "bidirectional"))
    )
    (net (code "164") (name "/RX2D7") (class "Default")
      (node (ref "U8") (pin "U4") (pinfunction "IO_L10P_3_U4") (pintype "bidirectional"))
    )
    (net (code "165") (name "/RX2D8") (class "Default")
      (node (ref "U8") (pin "V2") (pinfunction "IO_L32P_M3DQ14_3_V2") (pintype "bidirectional"))
    )
    (net (code "166") (name "/RX2D9") (class "Default")
      (node (ref "U8") (pin "V1") (pinfunction "IO_L32N_M3DQ15_3_V1") (pintype "bidirectional"))
    )
    (net (code "167") (name "/RX2D10") (class "Default")
      (node (ref "U8") (pin "W1") (pinfunction "IO_L2N_3_W1") (pintype "bidirectional"))
    )
    (net (code "168") (name "/RX2D11") (class "Default")
      (node (ref "U8") (pin "W3") (pinfunction "IO_L2P_3_W3") (pintype "bidirectional"))
    )
    (net (code "169") (name "/RX2IQSEL") (class "Default")
      (node (ref "U8") (pin "P8") (pinfunction "IO_L7P_3_P8") (pintype "bidirectional"))
    )
    (net (code "170") (name "/SCLK1") (class "Default")
      (node (ref "TST10") (pin "1") (pinfunction "1_1") (pintype "passive"))
      (node (ref "U8") (pin "F1") (pinfunction "IO_L50N_M3BA2_3_F1") (pintype "bidirectional"))
    )
    (net (code "171") (name "/SCLK2") (class "Default")
      (node (ref "TST14") (pin "1") (pinfunction "1_1") (pintype "passive"))
      (node (ref "U8") (pin "H5") (pinfunction "IO_L49N_M3A2_3_H5") (pintype "bidirectional"))
    )
    (net (code "172") (name "/SEN1") (class "Default")
      (node (ref "TST9") (pin "1") (pinfunction "1_1") (pintype "passive"))
      (node (ref "U8") (pin "E1") (pinfunction "IO_L52N_M3A9_3_E1") (pintype "bidirectional"))
    )
    (net (code "173") (name "/SEN2") (class "Default")
      (node (ref "TST13") (pin "1") (pinfunction "1_1") (pintype "passive"))
      (node (ref "U8") (pin "M4") (pinfunction "IO_L31N_VREF_3_M4") (pintype "bidirectional"))
    )
    (net (code "174") (name "/TX1D0") (class "Default")
      (node (ref "U8") (pin "H4") (pinfunction "IO_L46P_M3CLK_3_H4") (pintype "bidirectional"))
    )
    (net (code "175") (name "/TX1D1") (class "Default")
      (node (ref "U8") (pin "H8") (pinfunction "IO_L59N_3_H8") (pintype "bidirectional"))
    )
    (net (code "176") (name "/TX1D2") (class "Default")
      (node (ref "U8") (pin "G4") (pinfunction "IO_L51P_M3A10_3_G4") (pintype "bidirectional"))
    )
    (net (code "177") (name "/TX1D3") (class "Default")
      (node (ref "U8") (pin "G7") (pinfunction "IO_L80P_3_G7") (pintype "bidirectional"))
    )
    (net (code "178") (name "/TX1D4") (class "Default")
      (node (ref "U8") (pin "F5") (pinfunction "IO_L55N_M3A14_3_F5") (pintype "bidirectional"))
    )
    (net (code "179") (name "/TX1D5") (class "Default")
      (node (ref "U8") (pin "F7") (pinfunction "IO_L80N_3_F7") (pintype "bidirectional"))
    )
    (net (code "180") (name "/TX1D6") (class "Default")
      (node (ref "U8") (pin "G6") (pinfunction "IO_L55P_M3A13_3_G6") (pintype "bidirectional"))
    )
    (net (code "181") (name "/TX1D7") (class "Default")
      (node (ref "U8") (pin "E5") (pinfunction "IO_L82P_3_E5") (pintype "bidirectional"))
    )
    (net (code "182") (name "/TX1D8") (class "Default")
      (node (ref "U8") (pin "F3") (pinfunction "IO_L51N_M3A4_3_F3") (pintype "bidirectional"))
    )
    (net (code "183") (name "/TX1D9") (class "Default")
      (node (ref "U8") (pin "E4") (pinfunction "IO_L58N_3_E4") (pintype "bidirectional"))
    )
    (net (code "184") (name "/TX1D10") (class "Default")
      (node (ref "U8") (pin "H1") (pinfunction "IO_L47N_M3A1_3_H1") (pintype "bidirectional"))
    )
    (net (code "185") (name "/TX1D11") (class "Default")
      (node (ref "U8") (pin "E6") (pinfunction "IO_L82N_3_E6") (pintype "bidirectional"))
    )
    (net (code "186") (name "/TX1IQSEL") (class "Default")
      (node (ref "U8") (pin "H6") (pinfunction "IO_L49P_M3A7_3_H6") (pintype "bidirectional"))
    )
    (net (code "187") (name "/TX2D0") (class "Default")
      (node (ref "U8") (pin "R3") (pinfunction "IO_L35P_M3DQ10_3_R3") (pintype "bidirectional"))
    )
    (net (code "188") (name "/TX2D1") (class "Default")
      (node (ref "U8") (pin "L4") (pinfunction "IO_L42N_GCLK24_M3LDM_3_L4") (pintype "bidirectional"))
    )
    (net (code "189") (name "/TX2D2") (class "Default")
      (node (ref "U8") (pin "R1") (pinfunction "IO_L35N_M3DQ11_3_R1") (pintype "bidirectional"))
    )
    (net (code "190") (name "/TX2D3") (class "Default")
      (node (ref "U8") (pin "K7") (pinfunction "IO_L57P_3_K7") (pintype "bidirectional"))
    )
    (net (code "191") (name "/TX2D4") (class "Default")
      (node (ref "U8") (pin "P2") (pinfunction "IO_L36P_M3DQ8_3_P2") (pintype "bidirectional"))
    )
    (net (code "192") (name "/TX2D5") (class "Default")
      (node (ref "U8") (pin "K8") (pinfunction "IO_L57N_VREF_3_K8") (pintype "bidirectional"))
    )
    (net (code "193") (name "/TX2D6") (class "Default")
      (node (ref "U8") (pin "P1") (pinfunction "IO_L36N_M3DQ9_3_P1") (pintype "bidirectional"))
    )
    (net (code "194") (name "/TX2D7") (class "Default")
      (node (ref "U8") (pin "P4") (pinfunction "IO_L24N_3_P4") (pintype "bidirectional"))
    )
    (net (code "195") (name "/TX2D8") (class "Default")
      (node (ref "U8") (pin "P5") (pinfunction "IO_L8N_3_P5") (pintype "bidirectional"))
    )
    (net (code "196") (name "/TX2D9") (class "Default")
      (node (ref "U8") (pin "P6") (pinfunction "IO_L8P_3_P6") (pintype "bidirectional"))
    )
    (net (code "197") (name "/TX2D10") (class "Default")
      (node (ref "U8") (pin "P3") (pinfunction "IO_L26P_3_P3") (pintype "bidirectional"))
    )
    (net (code "198") (name "/TX2D11") (class "Default")
      (node (ref "U8") (pin "N3") (pinfunction "IO_L37P_M3DQ0_3_N3") (pintype "bidirectional"))
    )
    (net (code "199") (name "/TX2IQSEL") (class "Default")
      (node (ref "U8") (pin "M5") (pinfunction "IO_L31P_3_M5") (pintype "bidirectional"))
    )
    (net (code "200") (name "GND") (class "Default")
      (node (ref "R93") (pin "2") (pinfunction "2_2") (pintype "passive"))
      (node (ref "U11") (pin "31") (pinfunction "MODE_31") (pintype "passive"))
      (node (ref "U11") (pin "92") (pinfunction "~{CE}3_92") (pintype "passive"))
      (node (ref "U11") (pin "98") (pinfunction "~{CE}1_98") (pintype "passive"))
      (node (ref "X2-1") (pin "17") (pinfunction "17_17") (pintype "passive"))
      (node (ref "X2-2") (pin "18") (pinfunction "18_18") (pintype "passive"))
    )
    (net (code "201") (name "Net-(U8A-IO_L1P_HSWAPEN_0)") (class "Default")
      (node (ref "R93") (pin "1") (pinfunction "1_1") (pintype "passive"))
      (node (ref "U8") (pin "A3") (pinfunction "IO_L1P_HSWAPEN_0_A3") (pintype "bidirectional"))
    )
    (net (code "202") (name "unconnected-(U8B-IO_L9N_1-PadG17)") (class "Default")
      (node (ref "U8") (pin "G17") (pinfunction "IO_L9N_1_G17") (pintype "bidirectional+no_connect"))
    )
    (net (code "203") (name "unconnected-(U8B-IO_L28N_VREF_1-PadH17)") (class "Default")
      (node (ref "U8") (pin "H17") (pinfunction "IO_L28N_VREF_1_H17") (pintype "bidirectional+no_connect"))
    )
    (net (code "204") (name "unconnected-(U8B-IO_L46P_FCS_B_M1DQ2_1-PadM21)") (class "Default")
      (node (ref "U8") (pin "M21") (pinfunction "IO_L46P_FCS_B_M1DQ2_1_M21") (pintype "bidirectional+no_connect"))
    )
    (net (code "205") (name "unconnected-(U8B-IO_L47P_FWE_B_M1DQ0_1-PadN20)") (class "Default")
      (node (ref "U8") (pin "N20") (pinfunction "IO_L47P_FWE_B_M1DQ0_1_N20") (pintype "bidirectional+no_connect"))
    )
    (net (code "206") (name "unconnected-(U8B-IO_L48N_M1DQ9_1-PadP22)") (class "Default")
      (node (ref "U8") (pin "P22") (pinfunction "IO_L48N_M1DQ9_1_P22") (pintype "bidirectional+no_connect"))
    )
    (net (code "207") (name "unconnected-(U8B-IO_L48P_HDC_M1DQ8_1-PadP21)") (class "Default")
      (node (ref "U8") (pin "P21") (pinfunction "IO_L48P_HDC_M1DQ8_1_P21") (pintype "bidirectional+no_connect"))
    )
    (net (code "208") (name "unconnected-(U8B-IO_L58P_1-PadM16)") (class "Default")
      (node (ref "U8") (pin "M16") (pinfunction "IO_L58P_1_M16") (pintype "bidirectional+no_connect"))
    )
    (net (code "209") (name "unconnected-(U8B-IO_L59P_1-PadP19)") (class "Default")
      (node (ref "U8") (pin "P19") (pinfunction "IO_L59P_1_P19") (pintype "bidirectional+no_connect"))
    )
    (net (code "210") (name "unconnected-(U8B-IO_L70N_1-PadV20)") (class "Default")
      (node (ref "U8") (pin "V20") (pinfunction "IO_L70N_1_V20") (pintype "bidirectional+no_connect"))
    )
    (net (code "211") (name "unconnected-(U8B-IO_L70P_1-PadU19)") (class "Default")
      (node (ref "U8") (pin "U19") (pinfunction "IO_L70P_1_U19") (pintype "bidirectional+no_connect"))
    )
    (net (code "212") (name "unconnected-(U8B-IO_L71N_1-PadM18)") (class "Default")
      (node (ref "U8") (pin "M18") (pinfunction "IO_L71N_1_M18") (pintype "bidirectional+no_connect"))
    )
    (net (code "213") (name "unconnected-(U8B-IO_L71P_1-PadM17)") (class "Default")
      (node (ref "U8") (pin "M17") (pinfunction "IO_L71P_1_M17") (pintype "bidirectional+no_connect"))
    )
    (net (code "214") (name "unconnected-(U8B-IO_L72N_1-PadN16)") (class "Default")
      (node (ref "U8") (pin "N16") (pinfunction "IO_L72N_1_N16") (pintype "bidirectional+no_connect"))
    )
    (net (code "215") (name "unconnected-(U8B-IO_L72P_1-PadP17)") (class "Default")
      (node (ref "U8") (pin "P17") (pinfunction "IO_L72P_1_P17") (pintype "bidirectional+no_connect"))
    )
    (net (code "216") (name "unconnected-(U8B-IO_L73N_1-PadR19)") (class "Default")
      (node (ref "U8") (pin "R19") (pinfunction "IO_L73N_1_R19") (pintype "bidirectional+no_connect"))
    )
    (net (code "217") (name "unconnected-(U8B-IO_L73P_1-PadP18)") (class "Default")
      (node (ref "U8") (pin "P18") (pinfunction "IO_L73P_1_P18") (pintype "bidirectional+no_connect"))
    )
    (net (code "218") (name "unconnected-(U8B-IO_L74N_DOUT_BUSY_1-PadT20)") (class "Default")
      (node (ref "U8") (pin "T20") (pinfunction "IO_L74N_DOUT_BUSY_1_T20") (pintype "bidirectional+no_connect"))
    )
    (net (code "219") (name "unconnected-(U8D-IO_L1P_3-PadY2)") (class "Default")
      (node (ref "U8") (pin "Y2") (pinfunction "IO_L1P_3_Y2") (pintype "bidirectional+no_connect"))
    )
    (net (code "220") (name "unconnected-(U8D-IO_L7N_3-PadP7)") (class "Default")
      (node (ref "U8") (pin "P7") (pinfunction "IO_L7N_3_P7") (pintype "bidirectional+no_connect"))
    )
    (net (code "221") (name "unconnected-(U8D-IO_L24P_3-PadR4)") (class "Default")
      (node (ref "U8") (pin "R4") (pinfunction "IO_L24P_3_R4") (pintype "bidirectional+no_connect"))
    )
    (net (code "222") (name "unconnected-(U8D-IO_L25P_3-PadM6)") (class "Default")
      (node (ref "U8") (pin "M6") (pinfunction "IO_L25P_3_M6") (pintype "bidirectional+no_connect"))
    )
    (net (code "223") (name "unconnected-(U8D-IO_L26N_3-PadN4)") (class "Default")
      (node (ref "U8") (pin "N4") (pinfunction "IO_L26N_3_N4") (pintype "bidirectional+no_connect"))
    )
    (net (code "224") (name "unconnected-(U8D-IO_L37N_M3DQ1_3-PadN1)") (class "Default")
      (node (ref "U8") (pin "N1") (pinfunction "IO_L37N_M3DQ1_3_N1") (pintype "bidirectional+no_connect"))
    )
    (net (code "225") (name "unconnected-(U8D-IO_L39N_M3LDQSN_3-PadL1)") (class "Default")
      (node (ref "U8") (pin "L1") (pinfunction "IO_L39N_M3LDQSN_3_L1") (pintype "bidirectional+no_connect"))
    )
    (net (code "226") (name "unconnected-(U8D-IO_L44P_GCLK21_M3A5_3-PadK3)") (class "Default")
      (node (ref "U8") (pin "K3") (pinfunction "IO_L44P_GCLK21_M3A5_3_K3") (pintype "bidirectional+no_connect"))
    )
    (net (code "227") (name "unconnected-(U8D-IO_L48N_M3BA1_3-PadG1)") (class "Default")
      (node (ref "U8") (pin "G1") (pinfunction "IO_L48N_M3BA1_3_G1") (pintype "bidirectional+no_connect"))
    )
    (net (code "228") (name "unconnected-(U8D-IO_L48P_M3BA0_3-PadG3)") (class "Default")
      (node (ref "U8") (pin "G3") (pinfunction "IO_L48P_M3BA0_3_G3") (pintype "bidirectional+no_connect"))
    )
    (net (code "229") (name "unconnected-(U11A-NC(144)-Pad39)") (class "Default")
      (node (ref "U11") (pin "39") (pinfunction "NC(144)_39") (pintype "passive+no_connect"))
    )
    (net (code "230") (name "unconnected-(U11A-NC(288)-Pad38)") (class "Default")
      (node (ref "U11") (pin "38") (pinfunction "NC(288)_38") (pintype "passive+no_connect"))
    )
  )
)
